# HW4_SCHEMATIC.net
KiCad netlist of a schematic drawn in EAGLE
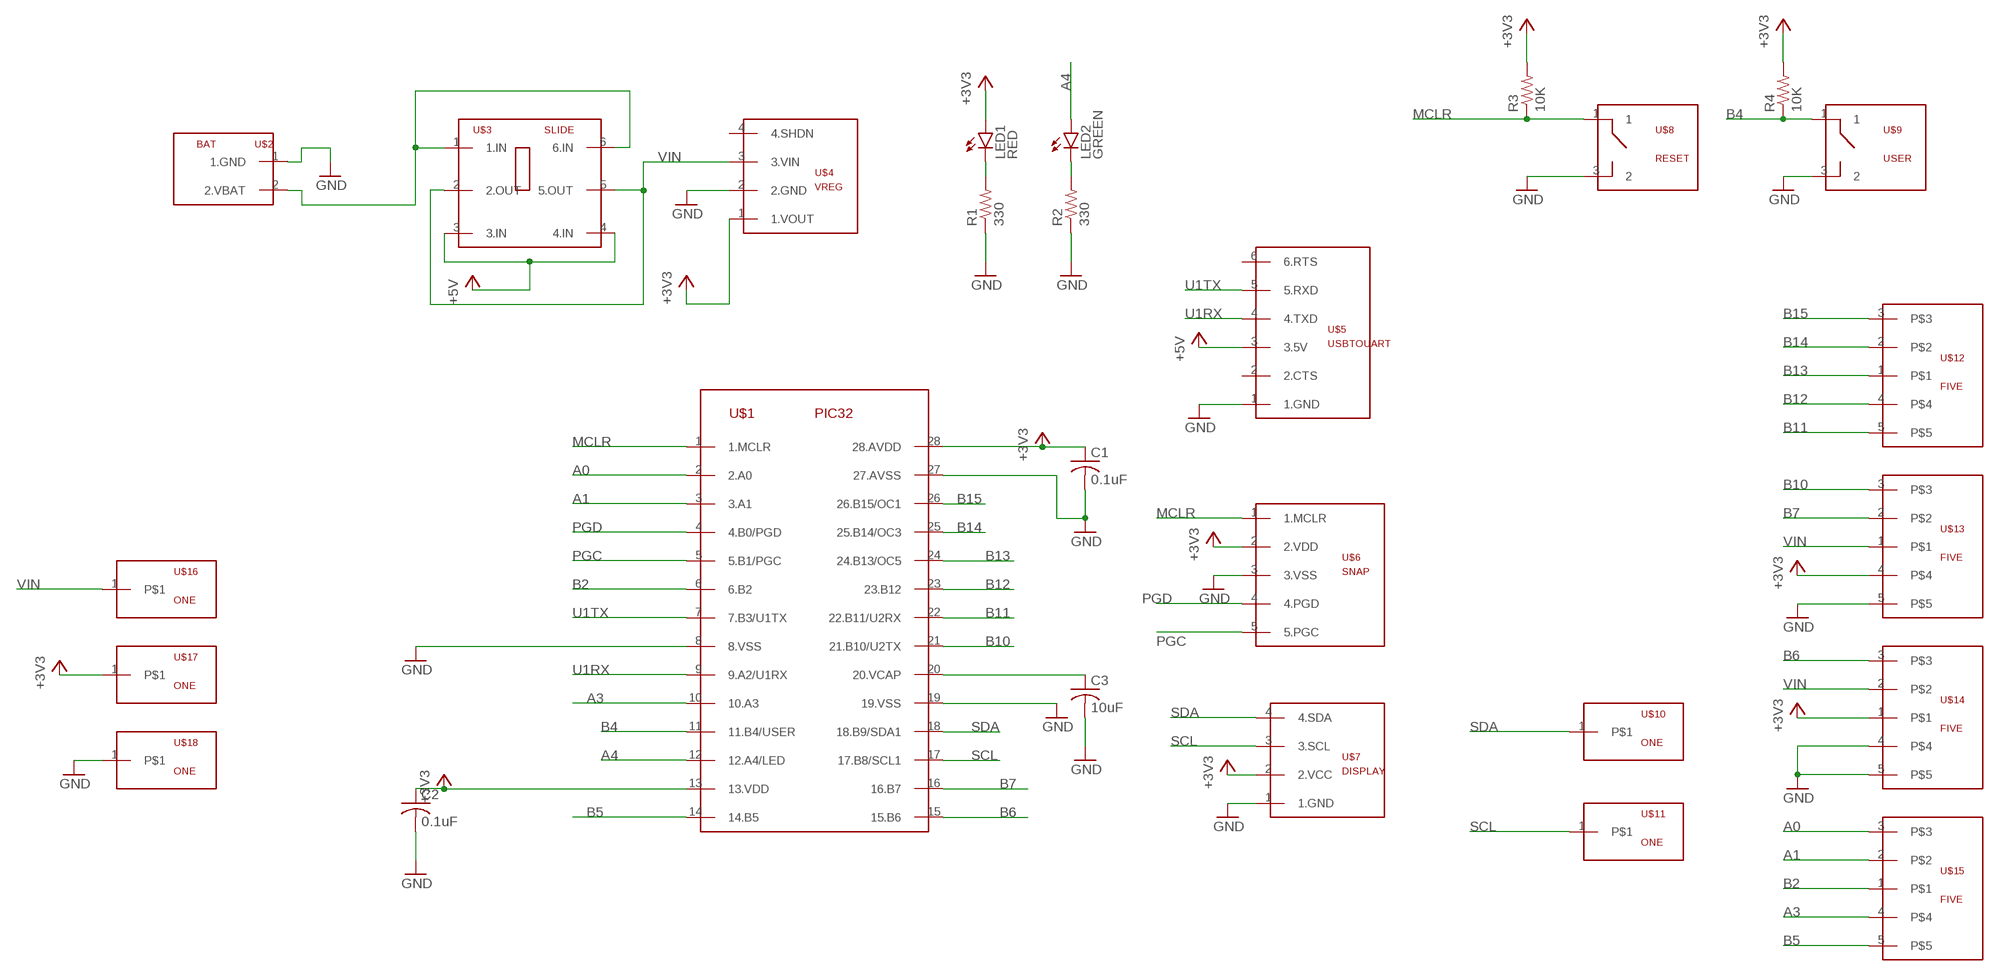
[diagram p0: schematic, sheet 1]

(export (version "E")
  (design (tool "Eeschema 10.0.6"))
  (components
    (comp (ref "C1")
      (value "0.1uF")
      (footprint "eagle-import:C025-024X044")
      (libsource (lib "eagle-import") (part "C-US025-024X044"))
    )
    (comp (ref "C2")
      (value "0.1uF")
      (footprint "eagle-import:C025-024X044")
      (libsource (lib "eagle-import") (part "C-US025-024X044"))
    )
    (comp (ref "C3")
      (value "10uF")
      (footprint "eagle-import:C025-024X044")
      (libsource (lib "eagle-import") (part "C-US025-024X044"))
    )
    (comp (ref "LED1")
      (value "RED")
      (footprint "eagle-import:LED3MM")
      (libsource (lib "eagle-import") (part "LED3MM"))
    )
    (comp (ref "LED2")
      (value "GREEN")
      (footprint "eagle-import:LED3MM")
      (libsource (lib "eagle-import") (part "LED3MM"))
    )
    (comp (ref "R1")
      (value "330")
      (footprint "eagle-import:0207_7")
      (libsource (lib "eagle-import") (part "R-US_0207/7"))
    )
    (comp (ref "R2")
      (value "330")
      (footprint "eagle-import:0207_7")
      (libsource (lib "eagle-import") (part "R-US_0207/7"))
    )
    (comp (ref "R3")
      (value "10K")
      (footprint "eagle-import:0207_7")
      (libsource (lib "eagle-import") (part "R-US_0207/7"))
    )
    (comp (ref "R4")
      (value "10K")
      (footprint "eagle-import:0207_7")
      (libsource (lib "eagle-import") (part "R-US_0207/7"))
    )
    (comp (ref "U$1")
      (value "PIC32")
      (footprint "eagle-import:DIL28-3")
      (libsource (lib "eagle-import") (part "PIC32"))
    )
    (comp (ref "U$2")
      (value "BAT")
      (footprint "eagle-import:BAT")
      (libsource (lib "eagle-import") (part "BAT"))
    )
    (comp (ref "U$3")
      (value "SLIDE")
      (footprint "eagle-import:SLIDE")
      (libsource (lib "eagle-import") (part "SLIDE"))
    )
    (comp (ref "U$4")
      (value "VREG")
      (footprint "eagle-import:VREG")
      (libsource (lib "eagle-import") (part "VREG"))
    )
    (comp (ref "U$5")
      (value "USBTOUART")
      (footprint "eagle-import:USBTOUART")
      (libsource (lib "eagle-import") (part "USBTOUART"))
    )
    (comp (ref "U$6")
      (value "SNAP")
      (footprint "eagle-import:SNAP")
      (libsource (lib "eagle-import") (part "SNAP"))
    )
    (comp (ref "U$7")
      (value "DISPLAY")
      (footprint "eagle-import:DISPLAY")
      (libsource (lib "eagle-import") (part "DISPLAY"))
    )
    (comp (ref "U$8")
      (value "RESET")
      (footprint "eagle-import:BUTTON")
      (libsource (lib "eagle-import") (part "BUTTON"))
    )
    (comp (ref "U$9")
      (value "USER")
      (footprint "eagle-import:BUTTON")
      (libsource (lib "eagle-import") (part "BUTTON"))
    )
    (comp (ref "U$10")
      (value "ONE")
      (footprint "eagle-import:ONE")
      (libsource (lib "eagle-import") (part "ONE"))
    )
    (comp (ref "U$11")
      (value "ONE")
      (footprint "eagle-import:ONE")
      (libsource (lib "eagle-import") (part "ONE"))
    )
    (comp (ref "U$12")
      (value "FIVE")
      (footprint "eagle-import:FIVE")
      (libsource (lib "eagle-import") (part "FIVE"))
    )
    (comp (ref "U$13")
      (value "FIVE")
      (footprint "eagle-import:FIVE")
      (libsource (lib "eagle-import") (part "FIVE"))
    )
    (comp (ref "U$14")
      (value "FIVE")
      (footprint "eagle-import:FIVE")
      (libsource (lib "eagle-import") (part "FIVE"))
    )
    (comp (ref "U$15")
      (value "FIVE")
      (footprint "eagle-import:FIVE")
      (libsource (lib "eagle-import") (part "FIVE"))
    )
    (comp (ref "U$16")
      (value "ONE")
      (footprint "eagle-import:ONE")
      (libsource (lib "eagle-import") (part "ONE"))
    )
    (comp (ref "U$17")
      (value "ONE")
      (footprint "eagle-import:ONE")
      (libsource (lib "eagle-import") (part "ONE"))
    )
    (comp (ref "U$18")
      (value "ONE")
      (footprint "eagle-import:ONE")
      (libsource (lib "eagle-import") (part "ONE"))
    )
  )
  (nets
    (net (code "1") (name "+3V3") (class "Default")
      (node (ref "C1") (pin "1") (pinfunction "1_1") (pintype "passive"))
      (node (ref "C2") (pin "1") (pinfunction "1_1") (pintype "passive"))
      (node (ref "LED1") (pin "A") (pinfunction "A_A") (pintype "passive"))
      (node (ref "R3") (pin "2") (pinfunction "2_2") (pintype "passive"))
      (node (ref "R4") (pin "2") (pinfunction "2_2") (pintype "passive"))
      (node (ref "U$1") (pin "13") (pinfunction "13.VDD_13") (pintype "bidirectional"))
      (node (ref "U$1") (pin "28") (pinfunction "28.AVDD_28") (pintype "bidirectional"))
      (node (ref "U$13") (pin "4") (pinfunction "P$4_4") (pintype "bidirectional"))
      (node (ref "U$14") (pin "1") (pinfunction "P$1_1") (pintype "bidirectional"))
      (node (ref "U$17") (pin "1") (pinfunction "P$1_1") (pintype "bidirectional"))
      (node (ref "U$4") (pin "1") (pinfunction "1.VOUT_1") (pintype "bidirectional"))
      (node (ref "U$6") (pin "2") (pinfunction "2.VDD_2") (pintype "bidirectional"))
      (node (ref "U$7") (pin "2") (pinfunction "2.VCC_2") (pintype "bidirectional"))
    )
    (net (code "2") (name "+5V") (class "Default")
      (node (ref "U$3") (pin "3") (pinfunction "3.IN_3") (pintype "bidirectional"))
      (node (ref "U$3") (pin "4") (pinfunction "4.IN_4") (pintype "bidirectional"))
      (node (ref "U$5") (pin "3") (pinfunction "3.5V_3") (pintype "bidirectional"))
    )
    (net (code "3") (name "/A0") (class "Default")
      (node (ref "U$1") (pin "2") (pinfunction "2.A0_2") (pintype "bidirectional"))
      (node (ref "U$15") (pin "3") (pinfunction "P$3_3") (pintype "bidirectional"))
    )
    (net (code "4") (name "/A1") (class "Default")
      (node (ref "U$1") (pin "3") (pinfunction "3.A1_3") (pintype "bidirectional"))
      (node (ref "U$15") (pin "2") (pinfunction "P$2_2") (pintype "bidirectional"))
    )
    (net (code "5") (name "/A3") (class "Default")
      (node (ref "U$1") (pin "10") (pinfunction "10.A3_10") (pintype "bidirectional"))
      (node (ref "U$15") (pin "4") (pinfunction "P$4_4") (pintype "bidirectional"))
    )
    (net (code "6") (name "/A4") (class "Default")
      (node (ref "LED2") (pin "A") (pinfunction "A_A") (pintype "passive"))
      (node (ref "U$1") (pin "12") (pinfunction "12.A4/LED_12") (pintype "bidirectional"))
    )
    (net (code "7") (name "/B2") (class "Default")
      (node (ref "U$1") (pin "6") (pinfunction "6.B2_6") (pintype "bidirectional"))
      (node (ref "U$15") (pin "1") (pinfunction "P$1_1") (pintype "bidirectional"))
    )
    (net (code "8") (name "/B4") (class "Default")
      (node (ref "R4") (pin "1") (pinfunction "1_1") (pintype "passive"))
      (node (ref "U$1") (pin "11") (pinfunction "11.B4/USER_11") (pintype "bidirectional"))
      (node (ref "U$9") (pin "1") (pinfunction "1_1") (pintype "bidirectional"))
    )
    (net (code "9") (name "/B5") (class "Default")
      (node (ref "U$1") (pin "14") (pinfunction "14.B5_14") (pintype "bidirectional"))
      (node (ref "U$15") (pin "5") (pinfunction "P$5_5") (pintype "bidirectional"))
    )
    (net (code "10") (name "/B6") (class "Default")
      (node (ref "U$1") (pin "15") (pinfunction "15.B6_15") (pintype "bidirectional"))
      (node (ref "U$14") (pin "3") (pinfunction "P$3_3") (pintype "bidirectional"))
    )
    (net (code "11") (name "/B7") (class "Default")
      (node (ref "U$1") (pin "16") (pinfunction "16.B7_16") (pintype "bidirectional"))
      (node (ref "U$13") (pin "2") (pinfunction "P$2_2") (pintype "bidirectional"))
    )
    (net (code "12") (name "/B10") (class "Default")
      (node (ref "U$1") (pin "21") (pinfunction "21.B10/U2TX_21") (pintype "bidirectional"))
      (node (ref "U$13") (pin "3") (pinfunction "P$3_3") (pintype "bidirectional"))
    )
    (net (code "13") (name "/B11") (class "Default")
      (node (ref "U$1") (pin "22") (pinfunction "22.B11/U2RX_22") (pintype "bidirectional"))
      (node (ref "U$12") (pin "5") (pinfunction "P$5_5") (pintype "bidirectional"))
    )
    (net (code "14") (name "/B12") (class "Default")
      (node (ref "U$1") (pin "23") (pinfunction "23.B12_23") (pintype "bidirectional"))
      (node (ref "U$12") (pin "4") (pinfunction "P$4_4") (pintype "bidirectional"))
    )
    (net (code "15") (name "/B13") (class "Default")
      (node (ref "U$1") (pin "24") (pinfunction "24.B13/OC5_24") (pintype "bidirectional"))
      (node (ref "U$12") (pin "1") (pinfunction "P$1_1") (pintype "bidirectional"))
    )
    (net (code "16") (name "/B14") (class "Default")
      (node (ref "U$1") (pin "25") (pinfunction "25.B14/OC3_25") (pintype "bidirectional"))
      (node (ref "U$12") (pin "2") (pinfunction "P$2_2") (pintype "bidirectional"))
    )
    (net (code "17") (name "/B15") (class "Default")
      (node (ref "U$1") (pin "26") (pinfunction "26.B15/OC1_26") (pintype "bidirectional"))
      (node (ref "U$12") (pin "3") (pinfunction "P$3_3") (pintype "bidirectional"))
    )
    (net (code "18") (name "/MCLR") (class "Default")
      (node (ref "R3") (pin "1") (pinfunction "1_1") (pintype "passive"))
      (node (ref "U$1") (pin "1") (pinfunction "1.MCLR_1") (pintype "bidirectional"))
      (node (ref "U$6") (pin "1") (pinfunction "1.MCLR_1") (pintype "bidirectional"))
      (node (ref "U$8") (pin "1") (pinfunction "1_1") (pintype "bidirectional"))
    )
    (net (code "19") (name "/PGC") (class "Default")
      (node (ref "U$1") (pin "5") (pinfunction "5.B1/PGC_5") (pintype "bidirectional"))
      (node (ref "U$6") (pin "5") (pinfunction "5.PGC_5") (pintype "bidirectional"))
    )
    (net (code "20") (name "/PGD") (class "Default")
      (node (ref "U$1") (pin "4") (pinfunction "4.B0/PGD_4") (pintype "bidirectional"))
      (node (ref "U$6") (pin "4") (pinfunction "4.PGD_4") (pintype "bidirectional"))
    )
    (net (code "21") (name "/SCL") (class "Default")
      (node (ref "U$1") (pin "17") (pinfunction "17.B8/SCL1_17") (pintype "bidirectional"))
      (node (ref "U$11") (pin "1") (pinfunction "P$1_1") (pintype "bidirectional"))
      (node (ref "U$7") (pin "3") (pinfunction "3.SCL_3") (pintype "bidirectional"))
    )
    (net (code "22") (name "/SDA") (class "Default")
      (node (ref "U$1") (pin "18") (pinfunction "18.B9/SDA1_18") (pintype "bidirectional"))
      (node (ref "U$10") (pin "1") (pinfunction "P$1_1") (pintype "bidirectional"))
      (node (ref "U$7") (pin "4") (pinfunction "4.SDA_4") (pintype "bidirectional"))
    )
    (net (code "23") (name "/U1RX") (class "Default")
      (node (ref "U$1") (pin "9") (pinfunction "9.A2/U1RX_9") (pintype "bidirectional"))
      (node (ref "U$5") (pin "4") (pinfunction "4.TXD_4") (pintype "bidirectional"))
    )
    (net (code "24") (name "/U1TX") (class "Default")
      (node (ref "U$1") (pin "7") (pinfunction "7.B3/U1TX_7") (pintype "bidirectional"))
      (node (ref "U$5") (pin "5") (pinfunction "5.RXD_5") (pintype "bidirectional"))
    )
    (net (code "25") (name "/VIN") (class "Default")
      (node (ref "U$13") (pin "1") (pinfunction "P$1_1") (pintype "bidirectional"))
      (node (ref "U$14") (pin "2") (pinfunction "P$2_2") (pintype "bidirectional"))
      (node (ref "U$16") (pin "1") (pinfunction "P$1_1") (pintype "bidirectional"))
      (node (ref "U$3") (pin "2") (pinfunction "2.OUT_2") (pintype "bidirectional"))
      (node (ref "U$3") (pin "5") (pinfunction "5.OUT_5") (pintype "bidirectional"))
      (node (ref "U$4") (pin "3") (pinfunction "3.VIN_3") (pintype "bidirectional"))
    )
    (net (code "26") (name "GND") (class "Default")
      (node (ref "C1") (pin "2") (pinfunction "2_2") (pintype "passive"))
      (node (ref "C2") (pin "2") (pinfunction "2_2") (pintype "passive"))
      (node (ref "C3") (pin "2") (pinfunction "2_2") (pintype "passive"))
      (node (ref "R1") (pin "1") (pinfunction "1_1") (pintype "passive"))
      (node (ref "R2") (pin "1") (pinfunction "1_1") (pintype "passive"))
      (node (ref "U$1") (pin "19") (pinfunction "19.VSS_19") (pintype "bidirectional"))
      (node (ref "U$1") (pin "27") (pinfunction "27.AVSS_27") (pintype "bidirectional"))
      (node (ref "U$1") (pin "8") (pinfunction "8.VSS_8") (pintype "bidirectional"))
      (node (ref "U$13") (pin "5") (pinfunction "P$5_5") (pintype "bidirectional"))
      (node (ref "U$14") (pin "4") (pinfunction "P$4_4") (pintype "bidirectional"))
      (node (ref "U$14") (pin "5") (pinfunction "P$5_5") (pintype "bidirectional"))
      (node (ref "U$18") (pin "1") (pinfunction "P$1_1") (pintype "bidirectional"))
      (node (ref "U$2") (pin "1") (pinfunction "1.GND_1") (pintype "bidirectional"))
      (node (ref "U$4") (pin "2") (pinfunction "2.GND_2") (pintype "bidirectional"))
      (node (ref "U$5") (pin "1") (pinfunction "1.GND_1") (pintype "bidirectional"))
      (node (ref "U$6") (pin "3") (pinfunction "3.VSS_3") (pintype "bidirectional"))
      (node (ref "U$7") (pin "1") (pinfunction "1.GND_1") (pintype "bidirectional"))
      (node (ref "U$8") (pin "3") (pinfunction "2_3") (pintype "bidirectional"))
      (node (ref "U$9") (pin "3") (pinfunction "2_3") (pintype "bidirectional"))
    )
    (net (code "27") (name "Net-(LED1-C)") (class "Default")
      (node (ref "LED1") (pin "K") (pinfunction "C_K") (pintype "passive"))
      (node (ref "R1") (pin "2") (pinfunction "2_2") (pintype "passive"))
    )
    (net (code "28") (name "Net-(LED2-C)") (class "Default")
      (node (ref "LED2") (pin "K") (pinfunction "C_K") (pintype "passive"))
      (node (ref "R2") (pin "2") (pinfunction "2_2") (pintype "passive"))
    )
    (net (code "29") (name "Net-(U$1-20.VCAP)") (class "Default")
      (node (ref "C3") (pin "1") (pinfunction "1_1") (pintype "passive"))
      (node (ref "U$1") (pin "20") (pinfunction "20.VCAP_20") (pintype "bidirectional"))
    )
    (net (code "30") (name "Net-(U$2-2.VBAT)") (class "Default")
      (node (ref "U$2") (pin "2") (pinfunction "2.VBAT_2") (pintype "bidirectional"))
      (node (ref "U$3") (pin "1") (pinfunction "1.IN_1") (pintype "bidirectional"))
      (node (ref "U$3") (pin "6") (pinfunction "6.IN_6") (pintype "bidirectional"))
    )
    (net (code "31") (name "unconnected-(U$4-4.SHDN-Pad4)") (class "Default")
      (node (ref "U$4") (pin "4") (pinfunction "4.SHDN_4") (pintype "bidirectional"))
    )
    (net (code "32") (name "unconnected-(U$5-2.CTS-Pad2)") (class "Default")
      (node (ref "U$5") (pin "2") (pinfunction "2.CTS_2") (pintype "bidirectional"))
    )
    (net (code "33") (name "unconnected-(U$5-6.RTS-Pad6)") (class "Default")
      (node (ref "U$5") (pin "6") (pinfunction "6.RTS_6") (pintype "bidirectional"))
    )
  )
)
